# Schematic_V2.net
KiCad netlist of a schematic drawn in EAGLE
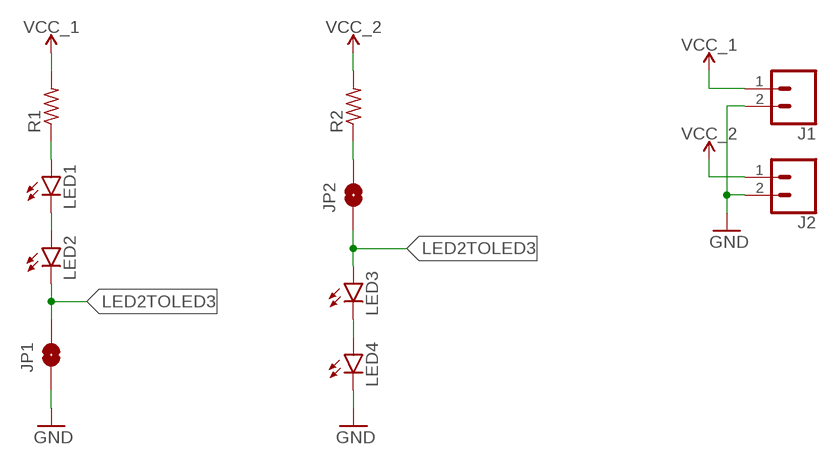
[diagram p0: schematic, sheet 1]

(export (version "E")
  (design (tool "Eeschema 10.0.6"))
  (components
    (comp (ref "J1")
      (value "CONN_02LOCK")
      (footprint "eagle-import:1X02_LOCK")
      (libsource (lib "eagle-import") (part "CONN_02LOCK"))
    )
    (comp (ref "J2")
      (value "CONN_02LOCK")
      (footprint "eagle-import:1X02_LOCK")
      (libsource (lib "eagle-import") (part "CONN_02LOCK"))
    )
    (comp (ref "JP1")
      (value "JUMPER-SMT_2_NO_SILK_ROUND")
      (footprint "eagle-import:SMT-JUMPER_2_NO_SILK_ROUND")
      (libsource (lib "eagle-import") (part "JUMPER-SMT_2_NO_SILK_ROUND"))
    )
    (comp (ref "JP2")
      (value "JUMPER-SMT_2_NO_SILK_ROUND")
      (footprint "eagle-import:SMT-JUMPER_2_NO_SILK_ROUND")
      (libsource (lib "eagle-import") (part "JUMPER-SMT_2_NO_SILK_ROUND"))
    )
    (comp (ref "LED1")
      (value "LED10MM")
      (footprint "eagle-import:LED10MM")
      (libsource (lib "eagle-import") (part "LED10MM"))
    )
    (comp (ref "LED2")
      (value "LED10MM")
      (footprint "eagle-import:LED10MM")
      (libsource (lib "eagle-import") (part "LED10MM"))
    )
    (comp (ref "LED3")
      (value "LED10MM")
      (footprint "eagle-import:LED10MM")
      (libsource (lib "eagle-import") (part "LED10MM"))
    )
    (comp (ref "LED4")
      (value "LED10MM")
      (footprint "eagle-import:LED10MM")
      (libsource (lib "eagle-import") (part "LED10MM"))
    )
    (comp (ref "R1")
      (value "R-US_0411/3V")
      (footprint "eagle-import:0411V")
      (libsource (lib "eagle-import") (part "R-US_0411/3V"))
    )
    (comp (ref "R2")
      (value "R-US_0411/3V")
      (footprint "eagle-import:0411V")
      (libsource (lib "eagle-import") (part "R-US_0411/3V"))
    )
  )
  (nets
    (net (code "1") (name "GND") (class "Default")
      (node (ref "J1") (pin "2") (pinfunction "2_2") (pintype "passive"))
      (node (ref "J2") (pin "2") (pinfunction "2_2") (pintype "passive"))
      (node (ref "JP1") (pin "1") (pinfunction "1_1") (pintype "passive"))
      (node (ref "LED4") (pin "K") (pinfunction "C_K") (pintype "passive"))
    )
    (net (code "2") (name "LED2TOLED3") (class "Default")
      (node (ref "JP1") (pin "2") (pinfunction "2_2") (pintype "passive"))
      (node (ref "JP2") (pin "1") (pinfunction "1_1") (pintype "passive"))
      (node (ref "LED2") (pin "K") (pinfunction "C_K") (pintype "passive"))
      (node (ref "LED3") (pin "A") (pinfunction "A_A") (pintype "passive"))
    )
    (net (code "3") (name "Net-(JP2-Pad2)") (class "Default")
      (node (ref "JP2") (pin "2") (pinfunction "2_2") (pintype "passive"))
      (node (ref "R2") (pin "1") (pinfunction "1_1") (pintype "passive"))
    )
    (net (code "4") (name "Net-(LED1-C)") (class "Default")
      (node (ref "LED1") (pin "K") (pinfunction "C_K") (pintype "passive"))
      (node (ref "LED2") (pin "A") (pinfunction "A_A") (pintype "passive"))
    )
    (net (code "5") (name "Net-(LED1-PadA)") (class "Default")
      (node (ref "LED1") (pin "A") (pinfunction "A_A") (pintype "passive"))
      (node (ref "R1") (pin "1") (pinfunction "1_1") (pintype "passive"))
    )
    (net (code "6") (name "Net-(LED3-C)") (class "Default")
      (node (ref "LED3") (pin "K") (pinfunction "C_K") (pintype "passive"))
      (node (ref "LED4") (pin "A") (pinfunction "A_A") (pintype "passive"))
    )
    (net (code "7") (name "VCC_1") (class "Default")
      (node (ref "J1") (pin "1") (pinfunction "1_1") (pintype "passive"))
      (node (ref "R1") (pin "2") (pinfunction "2_2") (pintype "passive"))
    )
    (net (code "8") (name "VCC_2") (class "Default")
      (node (ref "J2") (pin "1") (pinfunction "1_1") (pintype "passive"))
      (node (ref "R2") (pin "2") (pinfunction "2_2") (pintype "passive"))
    )
  )
)
